# Test_points.net
KiCad netlist of a schematic drawn in Altium Designer
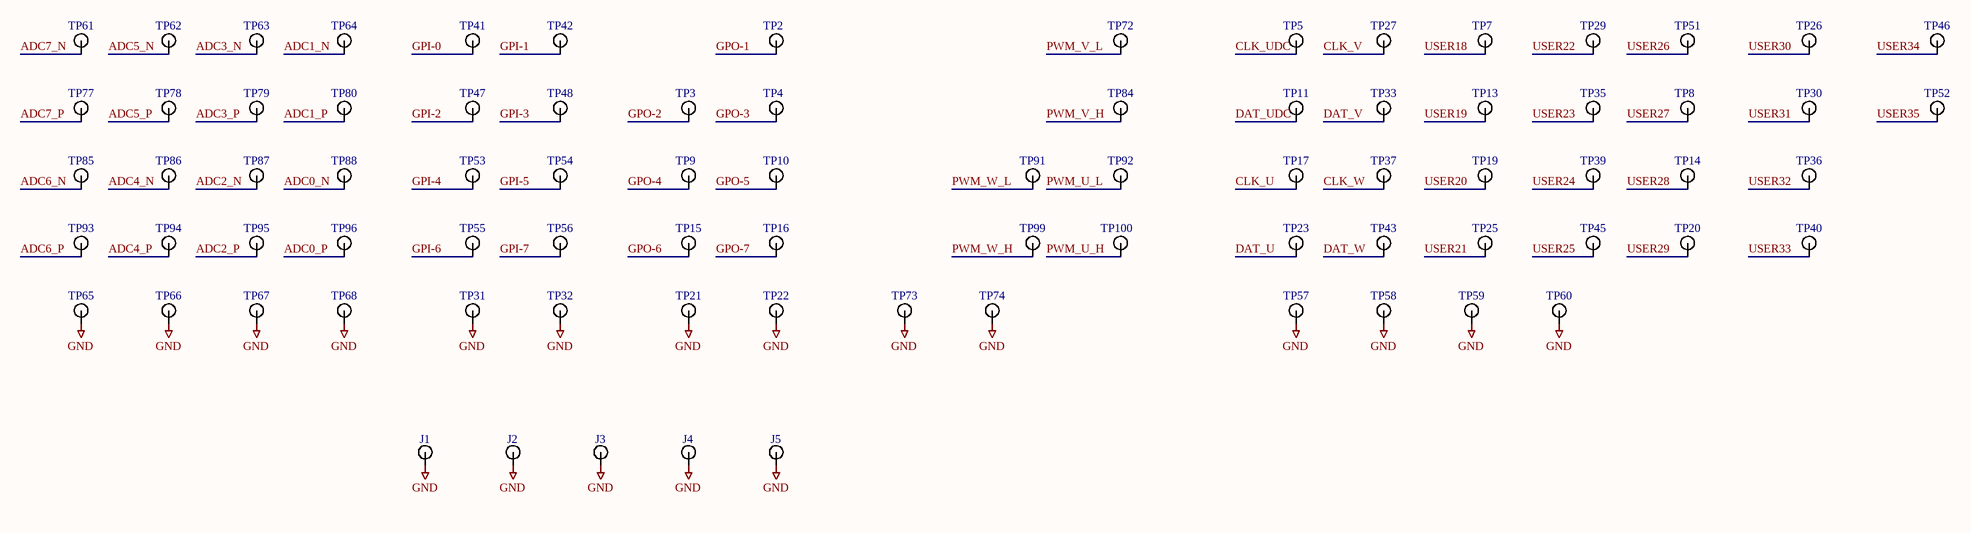
[diagram p0: Test points.SchDoc]

(export (version "E")
  (design (tool "Eeschema 10.0.6"))
  (components
    (comp (ref "J1")
      (value "1625854-1")
      (footprint "TP-3216L(1206)")
      (description "Natural PC Test Point Plating Surface Mount Mounting Type")
      (libsource (lib "CB3-ECB") (part "Testpoint"))
    )
    (comp (ref "J2")
      (value "1625854-1")
      (footprint "TP-3216L(1206)")
      (description "Natural PC Test Point Plating Surface Mount Mounting Type")
      (libsource (lib "CB3-ECB") (part "Testpoint"))
    )
    (comp (ref "J3")
      (value "1625854-1")
      (footprint "TP-3216L(1206)")
      (description "Natural PC Test Point Plating Surface Mount Mounting Type")
      (libsource (lib "CB3-ECB") (part "Testpoint"))
    )
    (comp (ref "J4")
      (value "1625854-1")
      (footprint "TP-3216L(1206)")
      (description "Natural PC Test Point Plating Surface Mount Mounting Type")
      (libsource (lib "CB3-ECB") (part "Testpoint"))
    )
    (comp (ref "J5")
      (value "1625854-1")
      (footprint "TP-3216L(1206)")
      (description "Natural PC Test Point Plating Surface Mount Mounting Type")
      (libsource (lib "CB3-ECB") (part "Testpoint"))
    )
    (comp (ref "TP2")
      (value "5001")
      (footprint "5001")
      (description "Black PC Test Point, Miniature Phosphor Bronze Silver Plating Through Hole Mounting Type")
      (libsource (lib "CB3-ECB") (part "Testpoint"))
    )
    (comp (ref "TP3")
      (value "5001")
      (footprint "5001")
      (description "Black PC Test Point, Miniature Phosphor Bronze Silver Plating Through Hole Mounting Type")
      (libsource (lib "CB3-ECB") (part "Testpoint"))
    )
    (comp (ref "TP4")
      (value "5001")
      (footprint "5001")
      (description "Black PC Test Point, Miniature Phosphor Bronze Silver Plating Through Hole Mounting Type")
      (libsource (lib "CB3-ECB") (part "Testpoint"))
    )
    (comp (ref "TP5")
      (value "5001")
      (footprint "5001")
      (description "Black PC Test Point, Miniature Phosphor Bronze Silver Plating Through Hole Mounting Type")
      (libsource (lib "CB3-ECB") (part "Testpoint"))
    )
    (comp (ref "TP7")
      (value "5001")
      (footprint "5001")
      (description "Black PC Test Point, Miniature Phosphor Bronze Silver Plating Through Hole Mounting Type")
      (libsource (lib "CB3-ECB") (part "Testpoint"))
    )
    (comp (ref "TP8")
      (value "5001")
      (footprint "5001")
      (description "Black PC Test Point, Miniature Phosphor Bronze Silver Plating Through Hole Mounting Type")
      (libsource (lib "CB3-ECB") (part "Testpoint"))
    )
    (comp (ref "TP9")
      (value "5001")
      (footprint "5001")
      (description "Black PC Test Point, Miniature Phosphor Bronze Silver Plating Through Hole Mounting Type")
      (libsource (lib "CB3-ECB") (part "Testpoint"))
    )
    (comp (ref "TP10")
      (value "5001")
      (footprint "5001")
      (description "Black PC Test Point, Miniature Phosphor Bronze Silver Plating Through Hole Mounting Type")
      (libsource (lib "CB3-ECB") (part "Testpoint"))
    )
    (comp (ref "TP11")
      (value "5001")
      (footprint "5001")
      (description "Black PC Test Point, Miniature Phosphor Bronze Silver Plating Through Hole Mounting Type")
      (libsource (lib "CB3-ECB") (part "Testpoint"))
    )
    (comp (ref "TP13")
      (value "5001")
      (footprint "5001")
      (description "Black PC Test Point, Miniature Phosphor Bronze Silver Plating Through Hole Mounting Type")
      (libsource (lib "CB3-ECB") (part "Testpoint"))
    )
    (comp (ref "TP14")
      (value "5001")
      (footprint "5001")
      (description "Black PC Test Point, Miniature Phosphor Bronze Silver Plating Through Hole Mounting Type")
      (libsource (lib "CB3-ECB") (part "Testpoint"))
    )
    (comp (ref "TP15")
      (value "5001")
      (footprint "5001")
      (description "Black PC Test Point, Miniature Phosphor Bronze Silver Plating Through Hole Mounting Type")
      (libsource (lib "CB3-ECB") (part "Testpoint"))
    )
    (comp (ref "TP16")
      (value "5001")
      (footprint "5001")
      (description "Black PC Test Point, Miniature Phosphor Bronze Silver Plating Through Hole Mounting Type")
      (libsource (lib "CB3-ECB") (part "Testpoint"))
    )
    (comp (ref "TP17")
      (value "5001")
      (footprint "5001")
      (description "Black PC Test Point, Miniature Phosphor Bronze Silver Plating Through Hole Mounting Type")
      (libsource (lib "CB3-ECB") (part "Testpoint"))
    )
    (comp (ref "TP19")
      (value "5001")
      (footprint "5001")
      (description "Black PC Test Point, Miniature Phosphor Bronze Silver Plating Through Hole Mounting Type")
      (libsource (lib "CB3-ECB") (part "Testpoint"))
    )
    (comp (ref "TP20")
      (value "5001")
      (footprint "5001")
      (description "Black PC Test Point, Miniature Phosphor Bronze Silver Plating Through Hole Mounting Type")
      (libsource (lib "CB3-ECB") (part "Testpoint"))
    )
    (comp (ref "TP21")
      (value "5001")
      (footprint "5001")
      (description "Black PC Test Point, Miniature Phosphor Bronze Silver Plating Through Hole Mounting Type")
      (libsource (lib "CB3-ECB") (part "Testpoint"))
    )
    (comp (ref "TP22")
      (value "5001")
      (footprint "5001")
      (description "Black PC Test Point, Miniature Phosphor Bronze Silver Plating Through Hole Mounting Type")
      (libsource (lib "CB3-ECB") (part "Testpoint"))
    )
    (comp (ref "TP23")
      (value "5001")
      (footprint "5001")
      (description "Black PC Test Point, Miniature Phosphor Bronze Silver Plating Through Hole Mounting Type")
      (libsource (lib "CB3-ECB") (part "Testpoint"))
    )
    (comp (ref "TP25")
      (value "5001")
      (footprint "5001")
      (description "Black PC Test Point, Miniature Phosphor Bronze Silver Plating Through Hole Mounting Type")
      (libsource (lib "CB3-ECB") (part "Testpoint"))
    )
    (comp (ref "TP26")
      (value "5001")
      (footprint "5001")
      (description "Black PC Test Point, Miniature Phosphor Bronze Silver Plating Through Hole Mounting Type")
      (libsource (lib "CB3-ECB") (part "Testpoint"))
    )
    (comp (ref "TP27")
      (value "5001")
      (footprint "5001")
      (description "Black PC Test Point, Miniature Phosphor Bronze Silver Plating Through Hole Mounting Type")
      (libsource (lib "CB3-ECB") (part "Testpoint"))
    )
    (comp (ref "TP29")
      (value "5001")
      (footprint "5001")
      (description "Black PC Test Point, Miniature Phosphor Bronze Silver Plating Through Hole Mounting Type")
      (libsource (lib "CB3-ECB") (part "Testpoint"))
    )
    (comp (ref "TP30")
      (value "5001")
      (footprint "5001")
      (description "Black PC Test Point, Miniature Phosphor Bronze Silver Plating Through Hole Mounting Type")
      (libsource (lib "CB3-ECB") (part "Testpoint"))
    )
    (comp (ref "TP31")
      (value "5001")
      (footprint "5001")
      (description "Black PC Test Point, Miniature Phosphor Bronze Silver Plating Through Hole Mounting Type")
      (libsource (lib "CB3-ECB") (part "Testpoint"))
    )
    (comp (ref "TP32")
      (value "5001")
      (footprint "5001")
      (description "Black PC Test Point, Miniature Phosphor Bronze Silver Plating Through Hole Mounting Type")
      (libsource (lib "CB3-ECB") (part "Testpoint"))
    )
    (comp (ref "TP33")
      (value "5001")
      (footprint "5001")
      (description "Black PC Test Point, Miniature Phosphor Bronze Silver Plating Through Hole Mounting Type")
      (libsource (lib "CB3-ECB") (part "Testpoint"))
    )
    (comp (ref "TP35")
      (value "5001")
      (footprint "5001")
      (description "Black PC Test Point, Miniature Phosphor Bronze Silver Plating Through Hole Mounting Type")
      (libsource (lib "CB3-ECB") (part "Testpoint"))
    )
    (comp (ref "TP36")
      (value "5001")
      (footprint "5001")
      (description "Black PC Test Point, Miniature Phosphor Bronze Silver Plating Through Hole Mounting Type")
      (libsource (lib "CB3-ECB") (part "Testpoint"))
    )
    (comp (ref "TP37")
      (value "5001")
      (footprint "5001")
      (description "Black PC Test Point, Miniature Phosphor Bronze Silver Plating Through Hole Mounting Type")
      (libsource (lib "CB3-ECB") (part "Testpoint"))
    )
    (comp (ref "TP39")
      (value "5001")
      (footprint "5001")
      (description "Black PC Test Point, Miniature Phosphor Bronze Silver Plating Through Hole Mounting Type")
      (libsource (lib "CB3-ECB") (part "Testpoint"))
    )
    (comp (ref "TP40")
      (value "5001")
      (footprint "5001")
      (description "Black PC Test Point, Miniature Phosphor Bronze Silver Plating Through Hole Mounting Type")
      (libsource (lib "CB3-ECB") (part "Testpoint"))
    )
    (comp (ref "TP41")
      (value "5001")
      (footprint "5001")
      (description "Black PC Test Point, Miniature Phosphor Bronze Silver Plating Through Hole Mounting Type")
      (libsource (lib "CB3-ECB") (part "Testpoint"))
    )
    (comp (ref "TP42")
      (value "5001")
      (footprint "5001")
      (description "Black PC Test Point, Miniature Phosphor Bronze Silver Plating Through Hole Mounting Type")
      (libsource (lib "CB3-ECB") (part "Testpoint"))
    )
    (comp (ref "TP43")
      (value "5001")
      (footprint "5001")
      (description "Black PC Test Point, Miniature Phosphor Bronze Silver Plating Through Hole Mounting Type")
      (libsource (lib "CB3-ECB") (part "Testpoint"))
    )
    (comp (ref "TP45")
      (value "5001")
      (footprint "5001")
      (description "Black PC Test Point, Miniature Phosphor Bronze Silver Plating Through Hole Mounting Type")
      (libsource (lib "CB3-ECB") (part "Testpoint"))
    )
    (comp (ref "TP46")
      (value "5001")
      (footprint "5001")
      (description "Black PC Test Point, Miniature Phosphor Bronze Silver Plating Through Hole Mounting Type")
      (libsource (lib "CB3-ECB") (part "Testpoint"))
    )
    (comp (ref "TP47")
      (value "5001")
      (footprint "5001")
      (description "Black PC Test Point, Miniature Phosphor Bronze Silver Plating Through Hole Mounting Type")
      (libsource (lib "CB3-ECB") (part "Testpoint"))
    )
    (comp (ref "TP48")
      (value "5001")
      (footprint "5001")
      (description "Black PC Test Point, Miniature Phosphor Bronze Silver Plating Through Hole Mounting Type")
      (libsource (lib "CB3-ECB") (part "Testpoint"))
    )
    (comp (ref "TP51")
      (value "5001")
      (footprint "5001")
      (description "Black PC Test Point, Miniature Phosphor Bronze Silver Plating Through Hole Mounting Type")
      (libsource (lib "CB3-ECB") (part "Testpoint"))
    )
    (comp (ref "TP52")
      (value "5001")
      (footprint "5001")
      (description "Black PC Test Point, Miniature Phosphor Bronze Silver Plating Through Hole Mounting Type")
      (libsource (lib "CB3-ECB") (part "Testpoint"))
    )
    (comp (ref "TP53")
      (value "5001")
      (footprint "5001")
      (description "Black PC Test Point, Miniature Phosphor Bronze Silver Plating Through Hole Mounting Type")
      (libsource (lib "CB3-ECB") (part "Testpoint"))
    )
    (comp (ref "TP54")
      (value "5001")
      (footprint "5001")
      (description "Black PC Test Point, Miniature Phosphor Bronze Silver Plating Through Hole Mounting Type")
      (libsource (lib "CB3-ECB") (part "Testpoint"))
    )
    (comp (ref "TP55")
      (value "5001")
      (footprint "5001")
      (description "Black PC Test Point, Miniature Phosphor Bronze Silver Plating Through Hole Mounting Type")
      (libsource (lib "CB3-ECB") (part "Testpoint"))
    )
    (comp (ref "TP56")
      (value "5001")
      (footprint "5001")
      (description "Black PC Test Point, Miniature Phosphor Bronze Silver Plating Through Hole Mounting Type")
      (libsource (lib "CB3-ECB") (part "Testpoint"))
    )
    (comp (ref "TP57")
      (value "5001")
      (footprint "5001")
      (description "Black PC Test Point, Miniature Phosphor Bronze Silver Plating Through Hole Mounting Type")
      (libsource (lib "CB3-ECB") (part "Testpoint"))
    )
    (comp (ref "TP58")
      (value "5001")
      (footprint "5001")
      (description "Black PC Test Point, Miniature Phosphor Bronze Silver Plating Through Hole Mounting Type")
      (libsource (lib "CB3-ECB") (part "Testpoint"))
    )
    (comp (ref "TP59")
      (value "5001")
      (footprint "5001")
      (description "Black PC Test Point, Miniature Phosphor Bronze Silver Plating Through Hole Mounting Type")
      (libsource (lib "CB3-ECB") (part "Testpoint"))
    )
    (comp (ref "TP60")
      (value "5001")
      (footprint "5001")
      (description "Black PC Test Point, Miniature Phosphor Bronze Silver Plating Through Hole Mounting Type")
      (libsource (lib "CB3-ECB") (part "Testpoint"))
    )
    (comp (ref "TP61")
      (value "5001")
      (footprint "5001")
      (description "Black PC Test Point, Miniature Phosphor Bronze Silver Plating Through Hole Mounting Type")
      (libsource (lib "CB3-ECB") (part "Testpoint"))
    )
    (comp (ref "TP62")
      (value "5001")
      (footprint "5001")
      (description "Black PC Test Point, Miniature Phosphor Bronze Silver Plating Through Hole Mounting Type")
      (libsource (lib "CB3-ECB") (part "Testpoint"))
    )
    (comp (ref "TP63")
      (value "5001")
      (footprint "5001")
      (description "Black PC Test Point, Miniature Phosphor Bronze Silver Plating Through Hole Mounting Type")
      (libsource (lib "CB3-ECB") (part "Testpoint"))
    )
    (comp (ref "TP64")
      (value "5001")
      (footprint "5001")
      (description "Black PC Test Point, Miniature Phosphor Bronze Silver Plating Through Hole Mounting Type")
      (libsource (lib "CB3-ECB") (part "Testpoint"))
    )
    (comp (ref "TP65")
      (value "5001")
      (footprint "5001")
      (description "Black PC Test Point, Miniature Phosphor Bronze Silver Plating Through Hole Mounting Type")
      (libsource (lib "CB3-ECB") (part "Testpoint"))
    )
    (comp (ref "TP66")
      (value "5001")
      (footprint "5001")
      (description "Black PC Test Point, Miniature Phosphor Bronze Silver Plating Through Hole Mounting Type")
      (libsource (lib "CB3-ECB") (part "Testpoint"))
    )
    (comp (ref "TP67")
      (value "5001")
      (footprint "5001")
      (description "Black PC Test Point, Miniature Phosphor Bronze Silver Plating Through Hole Mounting Type")
      (libsource (lib "CB3-ECB") (part "Testpoint"))
    )
    (comp (ref "TP68")
      (value "5001")
      (footprint "5001")
      (description "Black PC Test Point, Miniature Phosphor Bronze Silver Plating Through Hole Mounting Type")
      (libsource (lib "CB3-ECB") (part "Testpoint"))
    )
    (comp (ref "TP72")
      (value "5001")
      (footprint "5001")
      (description "Black PC Test Point, Miniature Phosphor Bronze Silver Plating Through Hole Mounting Type")
      (libsource (lib "CB3-ECB") (part "Testpoint"))
    )
    (comp (ref "TP73")
      (value "5001")
      (footprint "5001")
      (description "Black PC Test Point, Miniature Phosphor Bronze Silver Plating Through Hole Mounting Type")
      (libsource (lib "CB3-ECB") (part "Testpoint"))
    )
    (comp (ref "TP74")
      (value "5001")
      (footprint "5001")
      (description "Black PC Test Point, Miniature Phosphor Bronze Silver Plating Through Hole Mounting Type")
      (libsource (lib "CB3-ECB") (part "Testpoint"))
    )
    (comp (ref "TP77")
      (value "5001")
      (footprint "5001")
      (description "Black PC Test Point, Miniature Phosphor Bronze Silver Plating Through Hole Mounting Type")
      (libsource (lib "CB3-ECB") (part "Testpoint"))
    )
    (comp (ref "TP78")
      (value "5001")
      (footprint "5001")
      (description "Black PC Test Point, Miniature Phosphor Bronze Silver Plating Through Hole Mounting Type")
      (libsource (lib "CB3-ECB") (part "Testpoint"))
    )
    (comp (ref "TP79")
      (value "5001")
      (footprint "5001")
      (description "Black PC Test Point, Miniature Phosphor Bronze Silver Plating Through Hole Mounting Type")
      (libsource (lib "CB3-ECB") (part "Testpoint"))
    )
    (comp (ref "TP80")
      (value "5001")
      (footprint "5001")
      (description "Black PC Test Point, Miniature Phosphor Bronze Silver Plating Through Hole Mounting Type")
      (libsource (lib "CB3-ECB") (part "Testpoint"))
    )
    (comp (ref "TP84")
      (value "5001")
      (footprint "5001")
      (description "Black PC Test Point, Miniature Phosphor Bronze Silver Plating Through Hole Mounting Type")
      (libsource (lib "CB3-ECB") (part "Testpoint"))
    )
    (comp (ref "TP85")
      (value "5001")
      (footprint "5001")
      (description "Black PC Test Point, Miniature Phosphor Bronze Silver Plating Through Hole Mounting Type")
      (libsource (lib "CB3-ECB") (part "Testpoint"))
    )
    (comp (ref "TP86")
      (value "5001")
      (footprint "5001")
      (description "Black PC Test Point, Miniature Phosphor Bronze Silver Plating Through Hole Mounting Type")
      (libsource (lib "CB3-ECB") (part "Testpoint"))
    )
    (comp (ref "TP87")
      (value "5001")
      (footprint "5001")
      (description "Black PC Test Point, Miniature Phosphor Bronze Silver Plating Through Hole Mounting Type")
      (libsource (lib "CB3-ECB") (part "Testpoint"))
    )
    (comp (ref "TP88")
      (value "5001")
      (footprint "5001")
      (description "Black PC Test Point, Miniature Phosphor Bronze Silver Plating Through Hole Mounting Type")
      (libsource (lib "CB3-ECB") (part "Testpoint"))
    )
    (comp (ref "TP91")
      (value "5001")
      (footprint "5001")
      (description "Black PC Test Point, Miniature Phosphor Bronze Silver Plating Through Hole Mounting Type")
      (libsource (lib "CB3-ECB") (part "Testpoint"))
    )
    (comp (ref "TP92")
      (value "5001")
      (footprint "5001")
      (description "Black PC Test Point, Miniature Phosphor Bronze Silver Plating Through Hole Mounting Type")
      (libsource (lib "CB3-ECB") (part "Testpoint"))
    )
    (comp (ref "TP93")
      (value "5001")
      (footprint "5001")
      (description "Black PC Test Point, Miniature Phosphor Bronze Silver Plating Through Hole Mounting Type")
      (libsource (lib "CB3-ECB") (part "Testpoint"))
    )
    (comp (ref "TP94")
      (value "5001")
      (footprint "5001")
      (description "Black PC Test Point, Miniature Phosphor Bronze Silver Plating Through Hole Mounting Type")
      (libsource (lib "CB3-ECB") (part "Testpoint"))
    )
    (comp (ref "TP95")
      (value "5001")
      (footprint "5001")
      (description "Black PC Test Point, Miniature Phosphor Bronze Silver Plating Through Hole Mounting Type")
      (libsource (lib "CB3-ECB") (part "Testpoint"))
    )
    (comp (ref "TP96")
      (value "5001")
      (footprint "5001")
      (description "Black PC Test Point, Miniature Phosphor Bronze Silver Plating Through Hole Mounting Type")
      (libsource (lib "CB3-ECB") (part "Testpoint"))
    )
    (comp (ref "TP99")
      (value "5001")
      (footprint "5001")
      (description "Black PC Test Point, Miniature Phosphor Bronze Silver Plating Through Hole Mounting Type")
      (libsource (lib "CB3-ECB") (part "Testpoint"))
    )
    (comp (ref "TP100")
      (value "5001")
      (footprint "5001")
      (description "Black PC Test Point, Miniature Phosphor Bronze Silver Plating Through Hole Mounting Type")
      (libsource (lib "CB3-ECB") (part "Testpoint"))
    )
  )
  (nets
    (net (code "1") (name "/ADC0_N") (class "Default")
      (node (ref "TP88") (pin "1") (pinfunction "TP_1") (pintype "passive"))
    )
    (net (code "2") (name "/ADC0_P") (class "Default")
      (node (ref "TP96") (pin "1") (pinfunction "TP_1") (pintype "passive"))
    )
    (net (code "3") (name "/ADC1_N") (class "Default")
      (node (ref "TP64") (pin "1") (pinfunction "TP_1") (pintype "passive"))
    )
    (net (code "4") (name "/ADC1_P") (class "Default")
      (node (ref "TP80") (pin "1") (pinfunction "TP_1") (pintype "passive"))
    )
    (net (code "5") (name "/ADC2_N") (class "Default")
      (node (ref "TP87") (pin "1") (pinfunction "TP_1") (pintype "passive"))
    )
    (net (code "6") (name "/ADC2_P") (class "Default")
      (node (ref "TP95") (pin "1") (pinfunction "TP_1") (pintype "passive"))
    )
    (net (code "7") (name "/ADC3_N") (class "Default")
      (node (ref "TP63") (pin "1") (pinfunction "TP_1") (pintype "passive"))
    )
    (net (code "8") (name "/ADC3_P") (class "Default")
      (node (ref "TP79") (pin "1") (pinfunction "TP_1") (pintype "passive"))
    )
    (net (code "9") (name "/ADC4_N") (class "Default")
      (node (ref "TP86") (pin "1") (pinfunction "TP_1") (pintype "passive"))
    )
    (net (code "10") (name "/ADC4_P") (class "Default")
      (node (ref "TP94") (pin "1") (pinfunction "TP_1") (pintype "passive"))
    )
    (net (code "11") (name "/ADC5_N") (class "Default")
      (node (ref "TP62") (pin "1") (pinfunction "TP_1") (pintype "passive"))
    )
    (net (code "12") (name "/ADC5_P") (class "Default")
      (node (ref "TP78") (pin "1") (pinfunction "TP_1") (pintype "passive"))
    )
    (net (code "13") (name "/ADC6_N") (class "Default")
      (node (ref "TP85") (pin "1") (pinfunction "TP_1") (pintype "passive"))
    )
    (net (code "14") (name "/ADC6_P") (class "Default")
      (node (ref "TP93") (pin "1") (pinfunction "TP_1") (pintype "passive"))
    )
    (net (code "15") (name "/ADC7_N") (class "Default")
      (node (ref "TP61") (pin "1") (pinfunction "TP_1") (pintype "passive"))
    )
    (net (code "16") (name "/ADC7_P") (class "Default")
      (node (ref "TP77") (pin "1") (pinfunction "TP_1") (pintype "passive"))
    )
    (net (code "17") (name "/CLK_U") (class "Default")
      (node (ref "TP17") (pin "1") (pinfunction "TP_1") (pintype "passive"))
    )
    (net (code "18") (name "/CLK_UDC") (class "Default")
      (node (ref "TP5") (pin "1") (pinfunction "TP_1") (pintype "passive"))
    )
    (net (code "19") (name "/CLK_V") (class "Default")
      (node (ref "TP27") (pin "1") (pinfunction "TP_1") (pintype "passive"))
    )
    (net (code "20") (name "/CLK_W") (class "Default")
      (node (ref "TP37") (pin "1") (pinfunction "TP_1") (pintype "passive"))
    )
    (net (code "21") (name "/DAT_U") (class "Default")
      (node (ref "TP23") (pin "1") (pinfunction "TP_1") (pintype "passive"))
    )
    (net (code "22") (name "/DAT_UDC") (class "Default")
      (node (ref "TP11") (pin "1") (pinfunction "TP_1") (pintype "passive"))
    )
    (net (code "23") (name "/DAT_V") (class "Default")
      (node (ref "TP33") (pin "1") (pinfunction "TP_1") (pintype "passive"))
    )
    (net (code "24") (name "/DAT_W") (class "Default")
      (node (ref "TP43") (pin "1") (pinfunction "TP_1") (pintype "passive"))
    )
    (net (code "25") (name "/GPI-0") (class "Default")
      (node (ref "TP41") (pin "1") (pinfunction "TP_1") (pintype "passive"))
    )
    (net (code "26") (name "/GPI-1") (class "Default")
      (node (ref "TP42") (pin "1") (pinfunction "TP_1") (pintype "passive"))
    )
    (net (code "27") (name "/GPI-2") (class "Default")
      (node (ref "TP47") (pin "1") (pinfunction "TP_1") (pintype "passive"))
    )
    (net (code "28") (name "/GPI-3") (class "Default")
      (node (ref "TP48") (pin "1") (pinfunction "TP_1") (pintype "passive"))
    )
    (net (code "29") (name "/GPI-4") (class "Default")
      (node (ref "TP53") (pin "1") (pinfunction "TP_1") (pintype "passive"))
    )
    (net (code "30") (name "/GPI-5") (class "Default")
      (node (ref "TP54") (pin "1") (pinfunction "TP_1") (pintype "passive"))
    )
    (net (code "31") (name "/GPI-6") (class "Default")
      (node (ref "TP55") (pin "1") (pinfunction "TP_1") (pintype "passive"))
    )
    (net (code "32") (name "/GPI-7") (class "Default")
      (node (ref "TP56") (pin "1") (pinfunction "TP_1") (pintype "passive"))
    )
    (net (code "33") (name "/GPO-1") (class "Default")
      (node (ref "TP2") (pin "1") (pinfunction "TP_1") (pintype "passive"))
    )
    (net (code "34") (name "/GPO-2") (class "Default")
      (node (ref "TP3") (pin "1") (pinfunction "TP_1") (pintype "passive"))
    )
    (net (code "35") (name "/GPO-3") (class "Default")
      (node (ref "TP4") (pin "1") (pinfunction "TP_1") (pintype "passive"))
    )
    (net (code "36") (name "/GPO-4") (class "Default")
      (node (ref "TP9") (pin "1") (pinfunction "TP_1") (pintype "passive"))
    )
    (net (code "37") (name "/GPO-5") (class "Default")
      (node (ref "TP10") (pin "1") (pinfunction "TP_1") (pintype "passive"))
    )
    (net (code "38") (name "/GPO-6") (class "Default")
      (node (ref "TP15") (pin "1") (pinfunction "TP_1") (pintype "passive"))
    )
    (net (code "39") (name "/GPO-7") (class "Default")
      (node (ref "TP16") (pin "1") (pinfunction "TP_1") (pintype "passive"))
    )
    (net (code "40") (name "/PWM_U_H") (class "Default")
      (node (ref "TP100") (pin "1") (pinfunction "TP_1") (pintype "passive"))
    )
    (net (code "41") (name "/PWM_U_L") (class "Default")
      (node (ref "TP92") (pin "1") (pinfunction "TP_1") (pintype "passive"))
    )
    (net (code "42") (name "/PWM_V_H") (class "Default")
      (node (ref "TP84") (pin "1") (pinfunction "TP_1") (pintype "passive"))
    )
    (net (code "43") (name "/PWM_V_L") (class "Default")
      (node (ref "TP72") (pin "1") (pinfunction "TP_1") (pintype "passive"))
    )
    (net (code "44") (name "/PWM_W_H") (class "Default")
      (node (ref "TP99") (pin "1") (pinfunction "TP_1") (pintype "passive"))
    )
    (net (code "45") (name "/PWM_W_L") (class "Default")
      (node (ref "TP91") (pin "1") (pinfunction "TP_1") (pintype "passive"))
    )
    (net (code "46") (name "/USER18") (class "Default")
      (node (ref "TP7") (pin "1") (pinfunction "TP_1") (pintype "passive"))
    )
    (net (code "47") (name "/USER19") (class "Default")
      (node (ref "TP13") (pin "1") (pinfunction "TP_1") (pintype "passive"))
    )
    (net (code "48") (name "/USER20") (class "Default")
      (node (ref "TP19") (pin "1") (pinfunction "TP_1") (pintype "passive"))
    )
    (net (code "49") (name "/USER21") (class "Default")
      (node (ref "TP25") (pin "1") (pinfunction "TP_1") (pintype "passive"))
    )
    (net (code "50") (name "/USER22") (class "Default")
      (node (ref "TP29") (pin "1") (pinfunction "TP_1") (pintype "passive"))
    )
    (net (code "51") (name "/USER23") (class "Default")
      (node (ref "TP35") (pin "1") (pinfunction "TP_1") (pintype "passive"))
    )
    (net (code "52") (name "/USER24") (class "Default")
      (node (ref "TP39") (pin "1") (pinfunction "TP_1") (pintype "passive"))
    )
    (net (code "53") (name "/USER25") (class "Default")
      (node (ref "TP45") (pin "1") (pinfunction "TP_1") (pintype "passive"))
    )
    (net (code "54") (name "/USER26") (class "Default")
      (node (ref "TP51") (pin "1") (pinfunction "TP_1") (pintype "passive"))
    )
    (net (code "55") (name "/USER27") (class "Default")
      (node (ref "TP8") (pin "1") (pinfunction "TP_1") (pintype "passive"))
    )
    (net (code "56") (name "/USER28") (class "Default")
      (node (ref "TP14") (pin "1") (pinfunction "TP_1") (pintype "passive"))
    )
    (net (code "57") (name "/USER29") (class "Default")
      (node (ref "TP20") (pin "1") (pinfunction "TP_1") (pintype "passive"))
    )
    (net (code "58") (name "/USER30") (class "Default")
      (node (ref "TP26") (pin "1") (pinfunction "TP_1") (pintype "passive"))
    )
    (net (code "59") (name "/USER31") (class "Default")
      (node (ref "TP30") (pin "1") (pinfunction "TP_1") (pintype "passive"))
    )
    (net (code "60") (name "/USER32") (class "Default")
      (node (ref "TP36") (pin "1") (pinfunction "TP_1") (pintype "passive"))
    )
    (net (code "61") (name "/USER33") (class "Default")
      (node (ref "TP40") (pin "1") (pinfunction "TP_1") (pintype "passive"))
    )
    (net (code "62") (name "/USER34") (class "Default")
      (node (ref "TP46") (pin "1") (pinfunction "TP_1") (pintype "passive"))
    )
    (net (code "63") (name "/USER35") (class "Default")
      (node (ref "TP52") (pin "1") (pinfunction "TP_1") (pintype "passive"))
    )
    (net (code "64") (name "GND") (class "Default")
      (node (ref "J1") (pin "1") (pinfunction "TP_1") (pintype "passive"))
      (node (ref "J2") (pin "1") (pinfunction "TP_1") (pintype "passive"))
      (node (ref "J3") (pin "1") (pinfunction "TP_1") (pintype "passive"))
      (node (ref "J4") (pin "1") (pinfunction "TP_1") (pintype "passive"))
      (node (ref "J5") (pin "1") (pinfunction "TP_1") (pintype "passive"))
      (node (ref "TP21") (pin "1") (pinfunction "TP_1") (pintype "passive"))
      (node (ref "TP22") (pin "1") (pinfunction "TP_1") (pintype "passive"))
      (node (ref "TP31") (pin "1") (pinfunction "TP_1") (pintype "passive"))
      (node (ref "TP32") (pin "1") (pinfunction "TP_1") (pintype "passive"))
      (node (ref "TP57") (pin "1") (pinfunction "TP_1") (pintype "passive"))
      (node (ref "TP58") (pin "1") (pinfunction "TP_1") (pintype "passive"))
      (node (ref "TP59") (pin "1") (pinfunction "TP_1") (pintype "passive"))
      (node (ref "TP60") (pin "1") (pinfunction "TP_1") (pintype "passive"))
      (node (ref "TP65") (pin "1") (pinfunction "TP_1") (pintype "passive"))
      (node (ref "TP66") (pin "1") (pinfunction "TP_1") (pintype "passive"))
      (node (ref "TP67") (pin "1") (pinfunction "TP_1") (pintype "passive"))
      (node (ref "TP68") (pin "1") (pinfunction "TP_1") (pintype "passive"))
      (node (ref "TP73") (pin "1") (pinfunction "TP_1") (pintype "passive"))
      (node (ref "TP74") (pin "1") (pinfunction "TP_1") (pintype "passive"))
    )
  )
)
